# ARD-80A.net
KiCad netlist of a schematic drawn in EAGLE
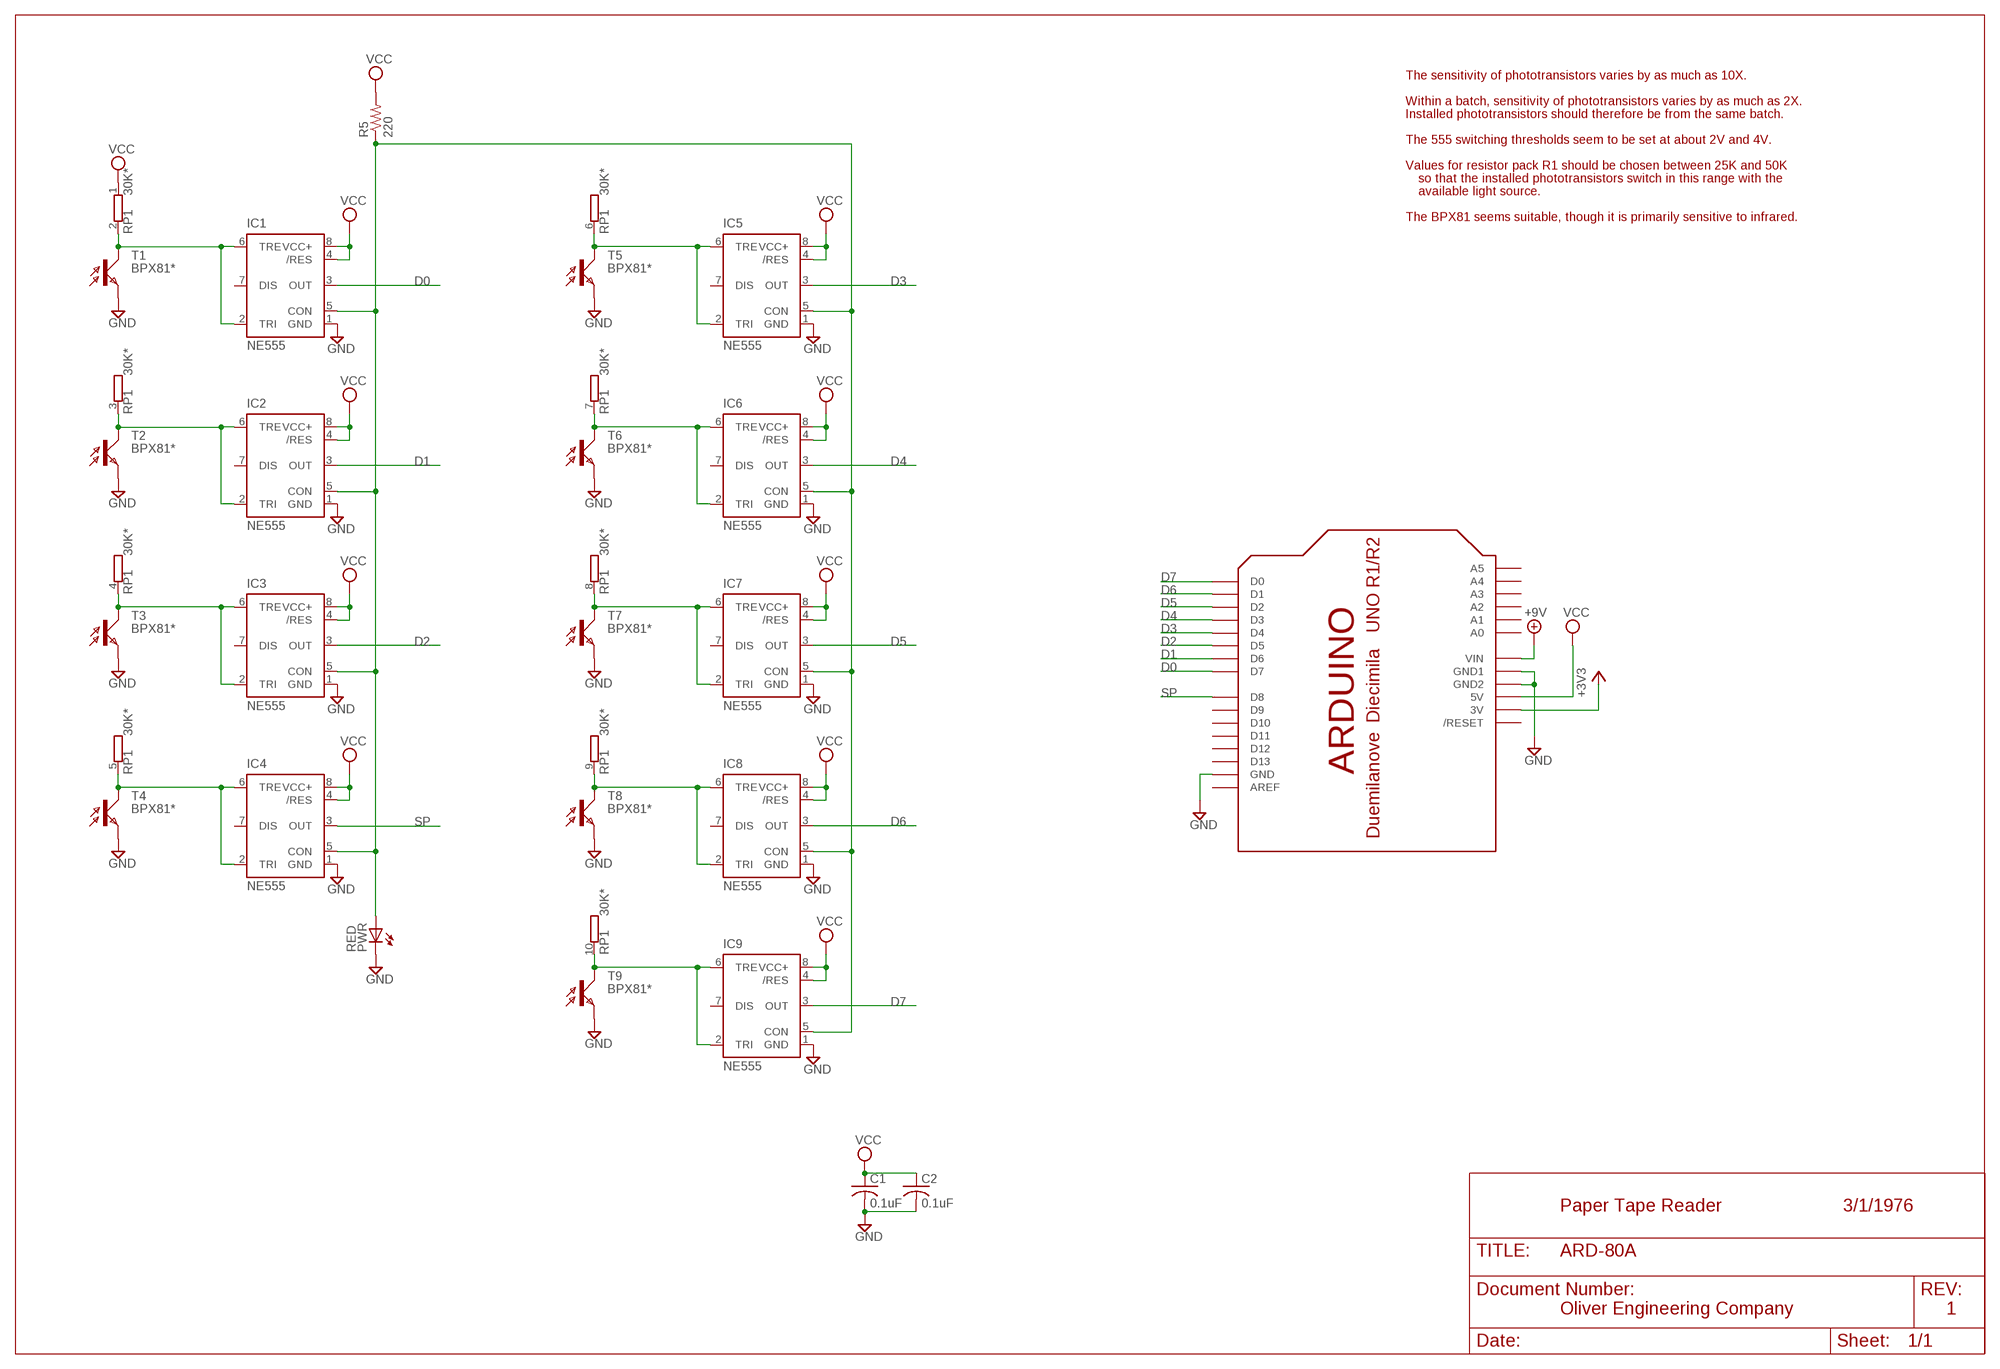
[diagram p0: schematic, sheet 1]

(export (version "E")
  (design (tool "Eeschema 10.0.6"))
  (components
    (comp (ref "C1")
      (value "0.1uF")
      (footprint "eagle-import:C050-030X075")
      (libsource (lib "eagle-import") (part "C-US050-030X075"))
    )
    (comp (ref "C2")
      (value "0.1uF")
      (footprint "eagle-import:C050-030X075")
      (libsource (lib "eagle-import") (part "C-US050-030X075"))
    )
    (comp (ref "IC1")
      (value "NE555")
      (footprint "eagle-import:DIL-08")
      (fields (field (name "MF") "Arrow Electronics") (field (name "MPN") "NE555N"))
      (libsource (lib "eagle-import") (part "NE555"))
    )
    (comp (ref "IC2")
      (value "NE555")
      (footprint "eagle-import:DIL-08")
      (fields (field (name "MF") "Arrow Electronics") (field (name "MPN") "NE555N"))
      (libsource (lib "eagle-import") (part "NE555"))
    )
    (comp (ref "IC3")
      (value "NE555")
      (footprint "eagle-import:DIL-08")
      (fields (field (name "MF") "Arrow Electronics") (field (name "MPN") "NE555N"))
      (libsource (lib "eagle-import") (part "NE555"))
    )
    (comp (ref "IC4")
      (value "NE555")
      (footprint "eagle-import:DIL-08")
      (fields (field (name "MF") "Arrow Electronics") (field (name "MPN") "NE555N"))
      (libsource (lib "eagle-import") (part "NE555"))
    )
    (comp (ref "IC5")
      (value "NE555")
      (footprint "eagle-import:DIL-08")
      (fields (field (name "MF") "Arrow Electronics") (field (name "MPN") "NE555N"))
      (libsource (lib "eagle-import") (part "NE555"))
    )
    (comp (ref "IC6")
      (value "NE555")
      (footprint "eagle-import:DIL-08")
      (fields (field (name "MF") "Arrow Electronics") (field (name "MPN") "NE555N"))
      (libsource (lib "eagle-import") (part "NE555"))
    )
    (comp (ref "IC7")
      (value "NE555")
      (footprint "eagle-import:DIL-08")
      (fields (field (name "MF") "Arrow Electronics") (field (name "MPN") "NE555N"))
      (libsource (lib "eagle-import") (part "NE555"))
    )
    (comp (ref "IC8")
      (value "NE555")
      (footprint "eagle-import:DIL-08")
      (fields (field (name "MF") "Arrow Electronics") (field (name "MPN") "NE555N"))
      (libsource (lib "eagle-import") (part "NE555"))
    )
    (comp (ref "IC9")
      (value "NE555")
      (footprint "eagle-import:DIL-08")
      (fields (field (name "MF") "Arrow Electronics") (field (name "MPN") "NE555N"))
      (libsource (lib "eagle-import") (part "NE555"))
    )
    (comp (ref "PWR")
      (value "RED")
      (footprint "eagle-import:LED5MM")
      (libsource (lib "eagle-import") (part "LED5MM"))
    )
    (comp (ref "R5")
      (value "220")
      (footprint "eagle-import:0207_10")
      (libsource (lib "eagle-import") (part "R-US_0207/10"))
    )
    (comp (ref "RP1")
      (value "30K*")
      (footprint "eagle-import:SIL10")
      (libsource (lib "eagle-import") (part "GE09RP"))
    )
    (comp (ref "T1")
      (value "BPX81*")
      (footprint "eagle-import:BPX81")
      (libsource (lib "eagle-import") (part "BPX81"))
    )
    (comp (ref "T2")
      (value "BPX81*")
      (footprint "eagle-import:BPX81")
      (libsource (lib "eagle-import") (part "BPX81"))
    )
    (comp (ref "T3")
      (value "BPX81*")
      (footprint "eagle-import:BPX81")
      (libsource (lib "eagle-import") (part "BPX81"))
    )
    (comp (ref "T4")
      (value "BPX81*")
      (footprint "eagle-import:BPX81")
      (libsource (lib "eagle-import") (part "BPX81"))
    )
    (comp (ref "T5")
      (value "BPX81*")
      (footprint "eagle-import:BPX81")
      (libsource (lib "eagle-import") (part "BPX81"))
    )
    (comp (ref "T6")
      (value "BPX81*")
      (footprint "eagle-import:BPX81")
      (libsource (lib "eagle-import") (part "BPX81"))
    )
    (comp (ref "T7")
      (value "BPX81*")
      (footprint "eagle-import:BPX81")
      (libsource (lib "eagle-import") (part "BPX81"))
    )
    (comp (ref "T8")
      (value "BPX81*")
      (footprint "eagle-import:BPX81")
      (libsource (lib "eagle-import") (part "BPX81"))
    )
    (comp (ref "T9")
      (value "BPX81*")
      (footprint "eagle-import:BPX81")
      (libsource (lib "eagle-import") (part "BPX81"))
    )
    (comp (ref "U$2")
      (value "ARDUINODUE")
      (footprint "eagle-import:ARDUINO_DUE_SHIELD")
      (libsource (lib "eagle-import") (part "ARDUINODUE"))
    )
  )
  (nets
    (net (code "1") (name "+3V3") (class "Default")
      (node (ref "U$2") (pin "3V3") (pinfunction "3V_3V3") (pintype "power_in"))
    )
    (net (code "2") (name "+9V") (class "Default")
      (node (ref "U$2") (pin "VIN") (pinfunction "VIN_VIN") (pintype "power_in"))
    )
    (net (code "3") (name "/D0") (class "Default")
      (node (ref "IC1") (pin "3") (pinfunction "OUT_3") (pintype "output"))
      (node (ref "U$2") (pin "7") (pinfunction "D7_7") (pintype "bidirectional"))
    )
    (net (code "4") (name "/D1") (class "Default")
      (node (ref "IC2") (pin "3") (pinfunction "OUT_3") (pintype "output"))
      (node (ref "U$2") (pin "6") (pinfunction "D6_6") (pintype "bidirectional"))
    )
    (net (code "5") (name "/D2") (class "Default")
      (node (ref "IC3") (pin "3") (pinfunction "OUT_3") (pintype "output"))
      (node (ref "U$2") (pin "5") (pinfunction "D5_5") (pintype "bidirectional"))
    )
    (net (code "6") (name "/D3") (class "Default")
      (node (ref "IC5") (pin "3") (pinfunction "OUT_3") (pintype "output"))
      (node (ref "U$2") (pin "4") (pinfunction "D4_4") (pintype "bidirectional"))
    )
    (net (code "7") (name "/D4") (class "Default")
      (node (ref "IC6") (pin "3") (pinfunction "OUT_3") (pintype "output"))
      (node (ref "U$2") (pin "3") (pinfunction "D3_3") (pintype "bidirectional"))
    )
    (net (code "8") (name "/D5") (class "Default")
      (node (ref "IC7") (pin "3") (pinfunction "OUT_3") (pintype "output"))
      (node (ref "U$2") (pin "2") (pinfunction "D2_2") (pintype "bidirectional"))
    )
    (net (code "9") (name "/D6") (class "Default")
      (node (ref "IC8") (pin "3") (pinfunction "OUT_3") (pintype "output"))
      (node (ref "U$2") (pin "1") (pinfunction "D1_1") (pintype "bidirectional"))
    )
    (net (code "10") (name "/D7") (class "Default")
      (node (ref "IC9") (pin "3") (pinfunction "OUT_3") (pintype "output"))
      (node (ref "U$2") (pin "0") (pinfunction "D0_0") (pintype "bidirectional"))
    )
    (net (code "11") (name "/SP") (class "Default")
      (node (ref "IC4") (pin "3") (pinfunction "OUT_3") (pintype "output"))
      (node (ref "U$2") (pin "8") (pinfunction "D8_8") (pintype "bidirectional"))
    )
    (net (code "12") (name "GND") (class "Default")
      (node (ref "C1") (pin "2") (pinfunction "2_2") (pintype "passive"))
      (node (ref "C2") (pin "2") (pinfunction "2_2") (pintype "passive"))
      (node (ref "IC1") (pin "1") (pinfunction "GND_1") (pintype "power_in"))
      (node (ref "IC2") (pin "1") (pinfunction "GND_1") (pintype "power_in"))
      (node (ref "IC3") (pin "1") (pinfunction "GND_1") (pintype "power_in"))
      (node (ref "IC4") (pin "1") (pinfunction "GND_1") (pintype "power_in"))
      (node (ref "IC5") (pin "1") (pinfunction "GND_1") (pintype "power_in"))
      (node (ref "IC6") (pin "1") (pinfunction "GND_1") (pintype "power_in"))
      (node (ref "IC7") (pin "1") (pinfunction "GND_1") (pintype "power_in"))
      (node (ref "IC8") (pin "1") (pinfunction "GND_1") (pintype "power_in"))
      (node (ref "IC9") (pin "1") (pinfunction "GND_1") (pintype "power_in"))
      (node (ref "PWR") (pin "K") (pinfunction "C_K") (pintype "passive"))
      (node (ref "T1") (pin "E") (pinfunction "E_E") (pintype "passive"))
      (node (ref "T2") (pin "E") (pinfunction "E_E") (pintype "passive"))
      (node (ref "T3") (pin "E") (pinfunction "E_E") (pintype "passive"))
      (node (ref "T4") (pin "E") (pinfunction "E_E") (pintype "passive"))
      (node (ref "T5") (pin "E") (pinfunction "E_E") (pintype "passive"))
      (node (ref "T6") (pin "E") (pinfunction "E_E") (pintype "passive"))
      (node (ref "T7") (pin "E") (pinfunction "E_E") (pintype "passive"))
      (node (ref "T8") (pin "E") (pinfunction "E_E") (pintype "passive"))
      (node (ref "T9") (pin "E") (pinfunction "E_E") (pintype "passive"))
      (node (ref "U$2") (pin "GND") (pinfunction "GND_GND") (pintype "power_in"))
      (node (ref "U$2") (pin "GND_1") (pinfunction "GND1_GND_1") (pintype "power_in"))
      (node (ref "U$2") (pin "GND_2") (pinfunction "GND2_GND_2") (pintype "power_in"))
    )
    (net (code "13") (name "Net-(IC1-CON)") (class "Default")
      (node (ref "IC1") (pin "5") (pinfunction "CON_5") (pintype "input"))
      (node (ref "IC2") (pin "5") (pinfunction "CON_5") (pintype "input"))
      (node (ref "IC3") (pin "5") (pinfunction "CON_5") (pintype "input"))
      (node (ref "IC4") (pin "5") (pinfunction "CON_5") (pintype "input"))
      (node (ref "IC5") (pin "5") (pinfunction "CON_5") (pintype "input"))
      (node (ref "IC6") (pin "5") (pinfunction "CON_5") (pintype "input"))
      (node (ref "IC7") (pin "5") (pinfunction "CON_5") (pintype "input"))
      (node (ref "IC8") (pin "5") (pinfunction "CON_5") (pintype "input"))
      (node (ref "IC9") (pin "5") (pinfunction "CON_5") (pintype "input"))
      (node (ref "PWR") (pin "A") (pinfunction "A_A") (pintype "passive"))
      (node (ref "R5") (pin "1") (pinfunction "1_1") (pintype "passive"))
    )
    (net (code "14") (name "Net-(IC1-TRE)") (class "Default")
      (node (ref "IC1") (pin "2") (pinfunction "TRI_2") (pintype "input"))
      (node (ref "IC1") (pin "6") (pinfunction "TRE_6") (pintype "input"))
      (node (ref "RP1") (pin "2") (pinfunction "2_2") (pintype "passive"))
      (node (ref "T1") (pin "C") (pinfunction "C_C") (pintype "passive"))
    )
    (net (code "15") (name "Net-(IC2-TRE)") (class "Default")
      (node (ref "IC2") (pin "2") (pinfunction "TRI_2") (pintype "input"))
      (node (ref "IC2") (pin "6") (pinfunction "TRE_6") (pintype "input"))
      (node (ref "RP1") (pin "3") (pinfunction "2_3") (pintype "passive"))
      (node (ref "T2") (pin "C") (pinfunction "C_C") (pintype "passive"))
    )
    (net (code "16") (name "Net-(IC3-TRE)") (class "Default")
      (node (ref "IC3") (pin "2") (pinfunction "TRI_2") (pintype "input"))
      (node (ref "IC3") (pin "6") (pinfunction "TRE_6") (pintype "input"))
      (node (ref "RP1") (pin "4") (pinfunction "2_4") (pintype "passive"))
      (node (ref "T3") (pin "C") (pinfunction "C_C") (pintype "passive"))
    )
    (net (code "17") (name "Net-(IC4-TRE)") (class "Default")
      (node (ref "IC4") (pin "2") (pinfunction "TRI_2") (pintype "input"))
      (node (ref "IC4") (pin "6") (pinfunction "TRE_6") (pintype "input"))
      (node (ref "RP1") (pin "5") (pinfunction "2_5") (pintype "passive"))
      (node (ref "T4") (pin "C") (pinfunction "C_C") (pintype "passive"))
    )
    (net (code "18") (name "Net-(IC5-TRE)") (class "Default")
      (node (ref "IC5") (pin "2") (pinfunction "TRI_2") (pintype "input"))
      (node (ref "IC5") (pin "6") (pinfunction "TRE_6") (pintype "input"))
      (node (ref "RP1") (pin "6") (pinfunction "2_6") (pintype "passive"))
      (node (ref "T5") (pin "C") (pinfunction "C_C") (pintype "passive"))
    )
    (net (code "19") (name "Net-(IC6-TRE)") (class "Default")
      (node (ref "IC6") (pin "2") (pinfunction "TRI_2") (pintype "input"))
      (node (ref "IC6") (pin "6") (pinfunction "TRE_6") (pintype "input"))
      (node (ref "RP1") (pin "7") (pinfunction "2_7") (pintype "passive"))
      (node (ref "T6") (pin "C") (pinfunction "C_C") (pintype "passive"))
    )
    (net (code "20") (name "Net-(IC7-TRE)") (class "Default")
      (node (ref "IC7") (pin "2") (pinfunction "TRI_2") (pintype "input"))
      (node (ref "IC7") (pin "6") (pinfunction "TRE_6") (pintype "input"))
      (node (ref "RP1") (pin "8") (pinfunction "2_8") (pintype "passive"))
      (node (ref "T7") (pin "C") (pinfunction "C_C") (pintype "passive"))
    )
    (net (code "21") (name "Net-(IC8-TRE)") (class "Default")
      (node (ref "IC8") (pin "2") (pinfunction "TRI_2") (pintype "input"))
      (node (ref "IC8") (pin "6") (pinfunction "TRE_6") (pintype "input"))
      (node (ref "RP1") (pin "9") (pinfunction "2_9") (pintype "passive"))
      (node (ref "T8") (pin "C") (pinfunction "C_C") (pintype "passive"))
    )
    (net (code "22") (name "Net-(IC9-TRE)") (class "Default")
      (node (ref "IC9") (pin "2") (pinfunction "TRI_2") (pintype "input"))
      (node (ref "IC9") (pin "6") (pinfunction "TRE_6") (pintype "input"))
      (node (ref "RP1") (pin "10") (pinfunction "2_10") (pintype "passive"))
      (node (ref "T9") (pin "C") (pinfunction "C_C") (pintype "passive"))
    )
    (net (code "23") (name "VCC") (class "Default")
      (node (ref "C1") (pin "1") (pinfunction "1_1") (pintype "passive"))
      (node (ref "C2") (pin "1") (pinfunction "1_1") (pintype "passive"))
      (node (ref "IC1") (pin "4") (pinfunction "/RES_4") (pintype "input"))
      (node (ref "IC1") (pin "8") (pinfunction "VCC+_8") (pintype "power_in"))
      (node (ref "IC2") (pin "4") (pinfunction "/RES_4") (pintype "input"))
      (node (ref "IC2") (pin "8") (pinfunction "VCC+_8") (pintype "power_in"))
      (node (ref "IC3") (pin "4") (pinfunction "/RES_4") (pintype "input"))
      (node (ref "IC3") (pin "8") (pinfunction "VCC+_8") (pintype "power_in"))
      (node (ref "IC4") (pin "4") (pinfunction "/RES_4") (pintype "input"))
      (node (ref "IC4") (pin "8") (pinfunction "VCC+_8") (pintype "power_in"))
      (node (ref "IC5") (pin "4") (pinfunction "/RES_4") (pintype "input"))
      (node (ref "IC5") (pin "8") (pinfunction "VCC+_8") (pintype "power_in"))
      (node (ref "IC6") (pin "4") (pinfunction "/RES_4") (pintype "input"))
      (node (ref "IC6") (pin "8") (pinfunction "VCC+_8") (pintype "power_in"))
      (node (ref "IC7") (pin "4") (pinfunction "/RES_4") (pintype "input"))
      (node (ref "IC7") (pin "8") (pinfunction "VCC+_8") (pintype "power_in"))
      (node (ref "IC8") (pin "4") (pinfunction "/RES_4") (pintype "input"))
      (node (ref "IC8") (pin "8") (pinfunction "VCC+_8") (pintype "power_in"))
      (node (ref "IC9") (pin "4") (pinfunction "/RES_4") (pintype "input"))
      (node (ref "IC9") (pin "8") (pinfunction "VCC+_8") (pintype "power_in"))
      (node (ref "R5") (pin "2") (pinfunction "2_2") (pintype "passive"))
      (node (ref "RP1") (pin "1") (pinfunction "1_1") (pintype "passive"))
      (node (ref "U$2") (pin "5V0") (pinfunction "5V_5V0") (pintype "power_in"))
    )
    (net (code "24") (name "unconnected-(IC1-DIS-Pad7)") (class "Default")
      (node (ref "IC1") (pin "7") (pinfunction "DIS_7") (pintype "output"))
    )
    (net (code "25") (name "unconnected-(IC2-DIS-Pad7)") (class "Default")
      (node (ref "IC2") (pin "7") (pinfunction "DIS_7") (pintype "output"))
    )
    (net (code "26") (name "unconnected-(IC3-DIS-Pad7)") (class "Default")
      (node (ref "IC3") (pin "7") (pinfunction "DIS_7") (pintype "output"))
    )
    (net (code "27") (name "unconnected-(IC4-DIS-Pad7)") (class "Default")
      (node (ref "IC4") (pin "7") (pinfunction "DIS_7") (pintype "output"))
    )
    (net (code "28") (name "unconnected-(IC5-DIS-Pad7)") (class "Default")
      (node (ref "IC5") (pin "7") (pinfunction "DIS_7") (pintype "output"))
    )
    (net (code "29") (name "unconnected-(IC6-DIS-Pad7)") (class "Default")
      (node (ref "IC6") (pin "7") (pinfunction "DIS_7") (pintype "output"))
    )
    (net (code "30") (name "unconnected-(IC7-DIS-Pad7)") (class "Default")
      (node (ref "IC7") (pin "7") (pinfunction "DIS_7") (pintype "output"))
    )
    (net (code "31") (name "unconnected-(IC8-DIS-Pad7)") (class "Default")
      (node (ref "IC8") (pin "7") (pinfunction "DIS_7") (pintype "output"))
    )
    (net (code "32") (name "unconnected-(IC9-DIS-Pad7)") (class "Default")
      (node (ref "IC9") (pin "7") (pinfunction "DIS_7") (pintype "output"))
    )
    (net (code "33") (name "unconnected-(U$2-D9-Pad9)") (class "Default")
      (node (ref "U$2") (pin "9") (pinfunction "D9_9") (pintype "bidirectional"))
    )
    (net (code "34") (name "unconnected-(U$2-D10-Pad10)") (class "Default")
      (node (ref "U$2") (pin "10") (pinfunction "D10_10") (pintype "bidirectional"))
    )
    (net (code "35") (name "unconnected-(U$2-D11-Pad11)") (class "Default")
      (node (ref "U$2") (pin "11") (pinfunction "D11_11") (pintype "bidirectional"))
    )
    (net (code "36") (name "unconnected-(U$2-D12-Pad12)") (class "Default")
      (node (ref "U$2") (pin "12") (pinfunction "D12_12") (pintype "bidirectional"))
    )
    (net (code "37") (name "unconnected-(U$2-D13-Pad13)") (class "Default")
      (node (ref "U$2") (pin "13") (pinfunction "D13_13") (pintype "bidirectional"))
    )
    (net (code "38") (name "unconnected-(U$2-PadA0)") (class "Default")
      (node (ref "U$2") (pin "A0") (pinfunction "A0_A0") (pintype "bidirectional"))
    )
    (net (code "39") (name "unconnected-(U$2-PadA1)") (class "Default")
      (node (ref "U$2") (pin "A1") (pinfunction "A1_A1") (pintype "bidirectional"))
    )
    (net (code "40") (name "unconnected-(U$2-PadA2)") (class "Default")
      (node (ref "U$2") (pin "A2") (pinfunction "A2_A2") (pintype "bidirectional"))
    )
    (net (code "41") (name "unconnected-(U$2-PadA3)") (class "Default")
      (node (ref "U$2") (pin "A3") (pinfunction "A3_A3") (pintype "bidirectional"))
    )
    (net (code "42") (name "unconnected-(U$2-PadA4)") (class "Default")
      (node (ref "U$2") (pin "A4") (pinfunction "A4_A4") (pintype "bidirectional"))
    )
    (net (code "43") (name "unconnected-(U$2-PadA5)") (class "Default")
      (node (ref "U$2") (pin "A5") (pinfunction "A5_A5") (pintype "bidirectional"))
    )
    (net (code "44") (name "unconnected-(U$2-PadAREF)") (class "Default")
      (node (ref "U$2") (pin "AREF") (pinfunction "AREF_AREF") (pintype "bidirectional"))
    )
    (net (code "45") (name "unconnected-(U$2-{slash}RESET-PadRESET)") (class "Default")
      (node (ref "U$2") (pin "RESET") (pinfunction "/RESET_RESET") (pintype "bidirectional"))
    )
  )
)
